# M623A.net
KiCad netlist of a schematic drawn in EAGLE
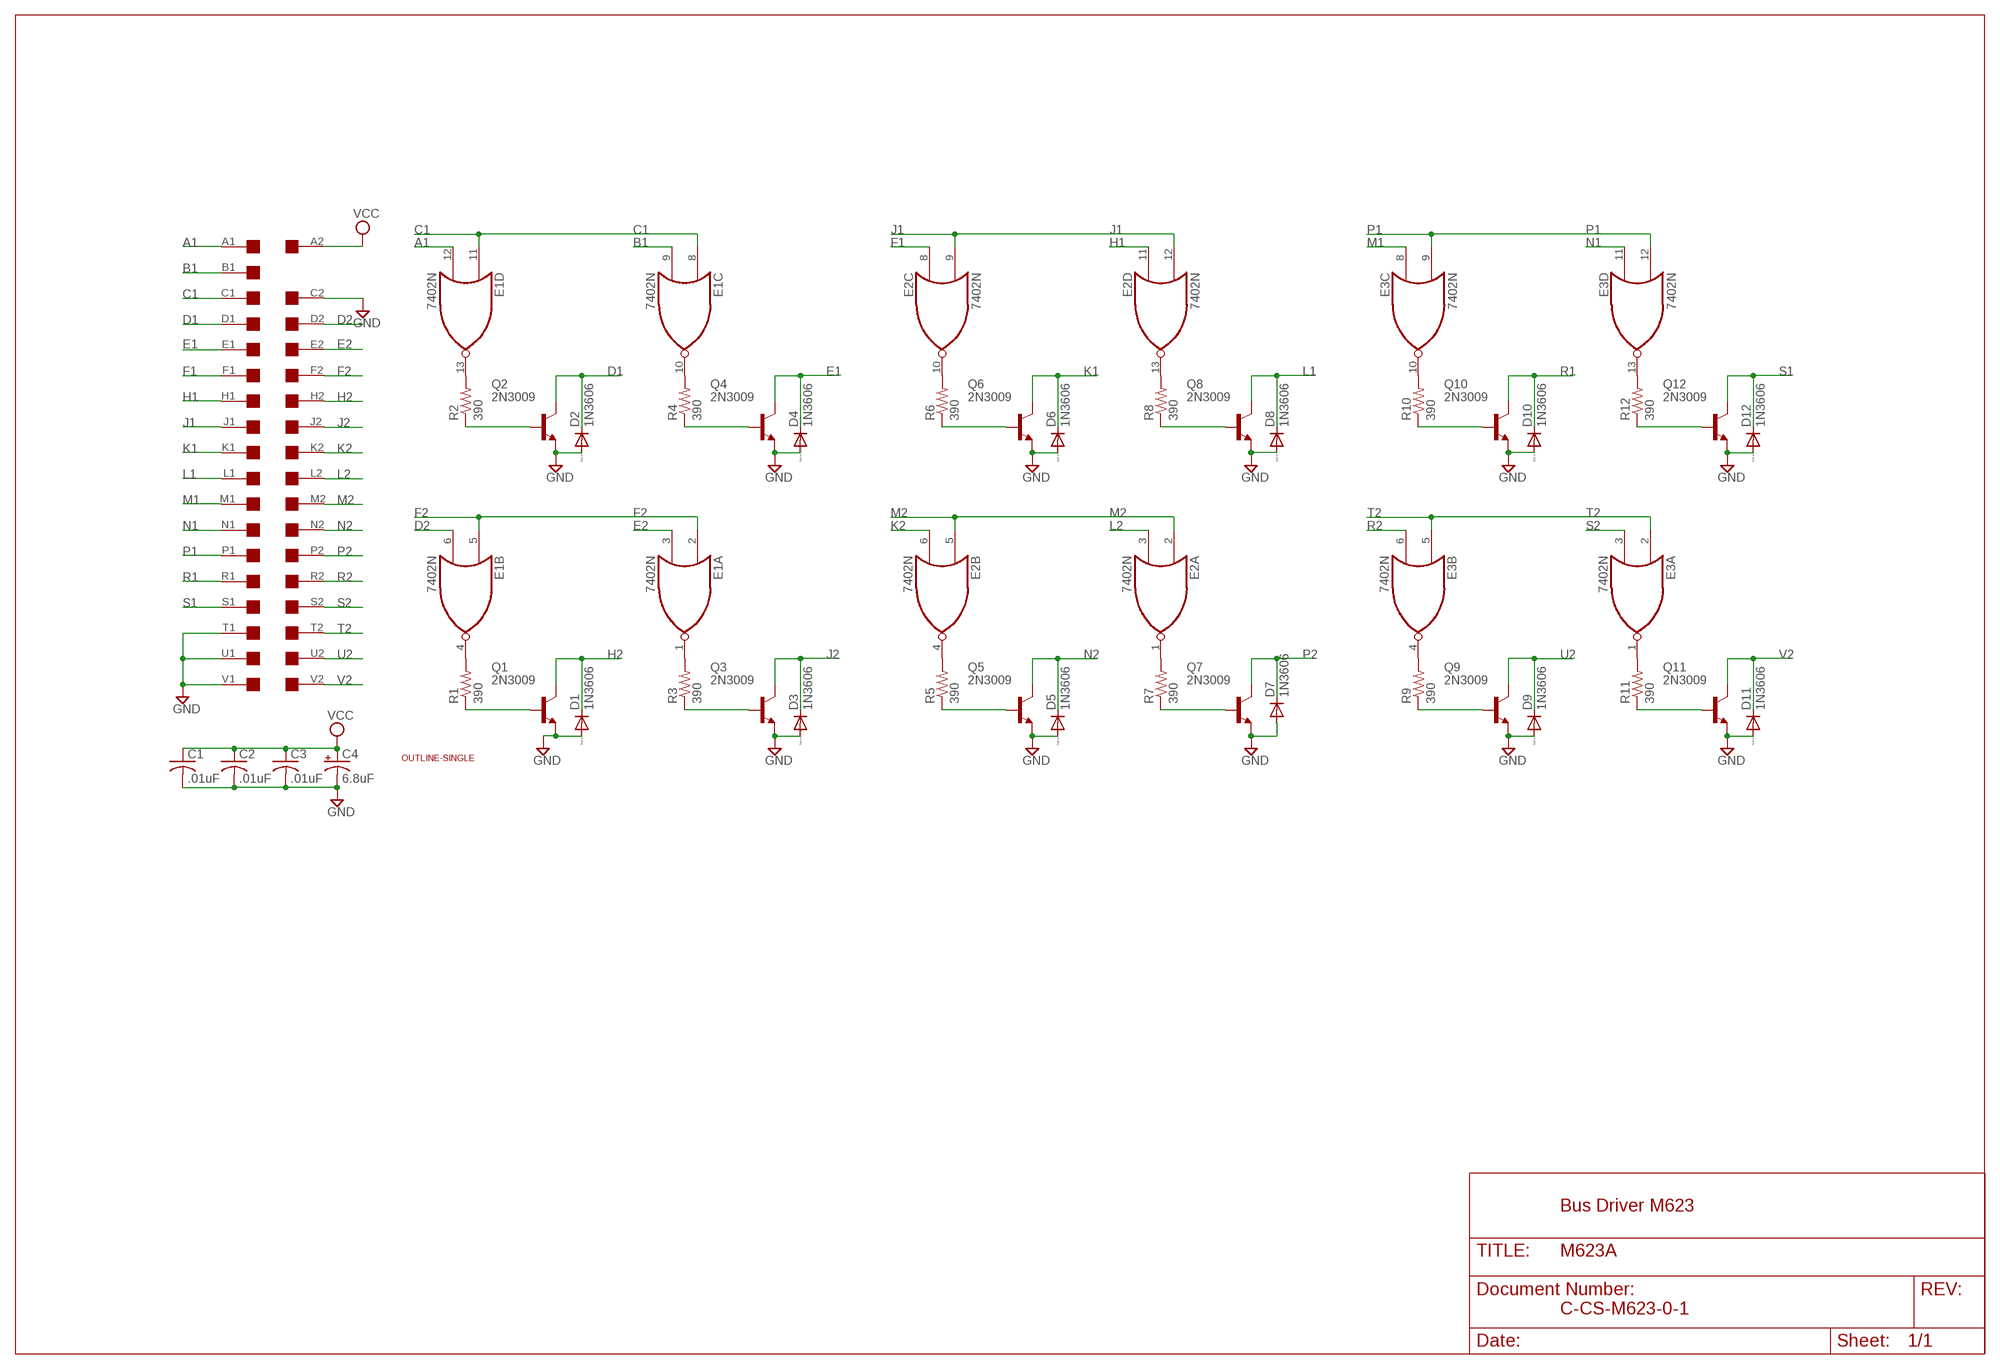
[diagram p0: schematic, sheet 1]

(export (version "E")
  (design (tool "Eeschema 10.0.6"))
  (components
    (comp (ref "C1")
      (value ".01uF")
      (footprint "eagle-import:C050-025X075")
      (libsource (lib "eagle-import") (part "C-US050-025X075"))
    )
    (comp (ref "C2")
      (value ".01uF")
      (footprint "eagle-import:C050-025X075")
      (libsource (lib "eagle-import") (part "C-US050-025X075"))
    )
    (comp (ref "C3")
      (value ".01uF")
      (footprint "eagle-import:C050-025X075")
      (libsource (lib "eagle-import") (part "C-US050-025X075"))
    )
    (comp (ref "C4")
      (value "6.8uF")
      (footprint "eagle-import:E15-5")
      (libsource (lib "eagle-import") (part "CPOL-USE15-5AXIAL"))
    )
    (comp (ref "D1")
      (value "1N3606")
      (footprint "eagle-import:DO35-10")
      (libsource (lib "eagle-import") (part "1N4148DO35-10"))
    )
    (comp (ref "D2")
      (value "1N3606")
      (footprint "eagle-import:DO35-10")
      (libsource (lib "eagle-import") (part "1N4148DO35-10"))
    )
    (comp (ref "D3")
      (value "1N3606")
      (footprint "eagle-import:DO35-10")
      (libsource (lib "eagle-import") (part "1N4148DO35-10"))
    )
    (comp (ref "D4")
      (value "1N3606")
      (footprint "eagle-import:DO35-10")
      (libsource (lib "eagle-import") (part "1N4148DO35-10"))
    )
    (comp (ref "D5")
      (value "1N3606")
      (footprint "eagle-import:DO35-10")
      (libsource (lib "eagle-import") (part "1N4148DO35-10"))
    )
    (comp (ref "D6")
      (value "1N3606")
      (footprint "eagle-import:DO35-10")
      (libsource (lib "eagle-import") (part "1N4148DO35-10"))
    )
    (comp (ref "D7")
      (value "1N3606")
      (footprint "eagle-import:DO35-10")
      (libsource (lib "eagle-import") (part "1N4148DO35-10"))
    )
    (comp (ref "D8")
      (value "1N3606")
      (footprint "eagle-import:DO35-10")
      (libsource (lib "eagle-import") (part "1N4148DO35-10"))
    )
    (comp (ref "D9")
      (value "1N3606")
      (footprint "eagle-import:DO35-10")
      (libsource (lib "eagle-import") (part "1N4148DO35-10"))
    )
    (comp (ref "D10")
      (value "1N3606")
      (footprint "eagle-import:DO35-10")
      (libsource (lib "eagle-import") (part "1N4148DO35-10"))
    )
    (comp (ref "D11")
      (value "1N3606")
      (footprint "eagle-import:DO35-10")
      (libsource (lib "eagle-import") (part "1N4148DO35-10"))
    )
    (comp (ref "D12")
      (value "1N3606")
      (footprint "eagle-import:DO35-10")
      (libsource (lib "eagle-import") (part "1N4148DO35-10"))
    )
    (comp (ref "E1")
      (value "7402N")
      (footprint "eagle-import:DIL14")
      (libsource (lib "eagle-import") (part "7402N"))
    )
    (comp (ref "E2")
      (value "7402N")
      (footprint "eagle-import:DIL14")
      (libsource (lib "eagle-import") (part "7402N"))
    )
    (comp (ref "E3")
      (value "7402N")
      (footprint "eagle-import:DIL14")
      (libsource (lib "eagle-import") (part "7402N"))
    )
    (comp (ref "Q1")
      (value "2N3009")
      (footprint "eagle-import:TO39")
      (libsource (lib "eagle-import") (part "-NPN-TO39-EBC2N1613"))
    )
    (comp (ref "Q2")
      (value "2N3009")
      (footprint "eagle-import:TO39")
      (libsource (lib "eagle-import") (part "-NPN-TO39-EBC2N1613"))
    )
    (comp (ref "Q3")
      (value "2N3009")
      (footprint "eagle-import:TO39")
      (libsource (lib "eagle-import") (part "-NPN-TO39-EBC2N1613"))
    )
    (comp (ref "Q4")
      (value "2N3009")
      (footprint "eagle-import:TO39")
      (libsource (lib "eagle-import") (part "-NPN-TO39-EBC2N1613"))
    )
    (comp (ref "Q5")
      (value "2N3009")
      (footprint "eagle-import:TO39")
      (libsource (lib "eagle-import") (part "-NPN-TO39-EBC2N1613"))
    )
    (comp (ref "Q6")
      (value "2N3009")
      (footprint "eagle-import:TO39")
      (libsource (lib "eagle-import") (part "-NPN-TO39-EBC2N1613"))
    )
    (comp (ref "Q7")
      (value "2N3009")
      (footprint "eagle-import:TO39")
      (libsource (lib "eagle-import") (part "-NPN-TO39-EBC2N1613"))
    )
    (comp (ref "Q8")
      (value "2N3009")
      (footprint "eagle-import:TO39")
      (libsource (lib "eagle-import") (part "-NPN-TO39-EBC2N1613"))
    )
    (comp (ref "Q9")
      (value "2N3009")
      (footprint "eagle-import:TO39")
      (libsource (lib "eagle-import") (part "-NPN-TO39-EBC2N1613"))
    )
    (comp (ref "Q10")
      (value "2N3009")
      (footprint "eagle-import:TO39")
      (libsource (lib "eagle-import") (part "-NPN-TO39-EBC2N1613"))
    )
    (comp (ref "Q11")
      (value "2N3009")
      (footprint "eagle-import:TO39")
      (libsource (lib "eagle-import") (part "-NPN-TO39-EBC2N1613"))
    )
    (comp (ref "Q12")
      (value "2N3009")
      (footprint "eagle-import:TO39")
      (libsource (lib "eagle-import") (part "-NPN-TO39-EBC2N1613"))
    )
    (comp (ref "R1")
      (value "390")
      (footprint "eagle-import:0207_10")
      (libsource (lib "eagle-import") (part "R-US_0207/10"))
    )
    (comp (ref "R2")
      (value "390")
      (footprint "eagle-import:0207_10")
      (libsource (lib "eagle-import") (part "R-US_0207/10"))
    )
    (comp (ref "R3")
      (value "390")
      (footprint "eagle-import:0207_10")
      (libsource (lib "eagle-import") (part "R-US_0207/10"))
    )
    (comp (ref "R4")
      (value "390")
      (footprint "eagle-import:0207_10")
      (libsource (lib "eagle-import") (part "R-US_0207/10"))
    )
    (comp (ref "R5")
      (value "390")
      (footprint "eagle-import:0207_10")
      (libsource (lib "eagle-import") (part "R-US_0207/10"))
    )
    (comp (ref "R6")
      (value "390")
      (footprint "eagle-import:0207_10")
      (libsource (lib "eagle-import") (part "R-US_0207/10"))
    )
    (comp (ref "R7")
      (value "390")
      (footprint "eagle-import:0207_10")
      (libsource (lib "eagle-import") (part "R-US_0207/10"))
    )
    (comp (ref "R8")
      (value "390")
      (footprint "eagle-import:0207_10")
      (libsource (lib "eagle-import") (part "R-US_0207/10"))
    )
    (comp (ref "R9")
      (value "390")
      (footprint "eagle-import:0207_10")
      (libsource (lib "eagle-import") (part "R-US_0207/10"))
    )
    (comp (ref "R10")
      (value "390")
      (footprint "eagle-import:0207_10")
      (libsource (lib "eagle-import") (part "R-US_0207/10"))
    )
    (comp (ref "R11")
      (value "390")
      (footprint "eagle-import:0207_10")
      (libsource (lib "eagle-import") (part "R-US_0207/10"))
    )
    (comp (ref "R12")
      (value "390")
      (footprint "eagle-import:0207_10")
      (libsource (lib "eagle-import") (part "R-US_0207/10"))
    )
    (comp (ref "U$1")
      (value "OUTLINE-SINGLE")
      (footprint "eagle-import:SINGLE")
      (libsource (lib "eagle-import") (part "OUTLINE-SINGLE"))
    )
    (comp (ref "U$4")
      (value "SINGLE")
      (footprint "eagle-import:EDGE-CON2")
      (libsource (lib "eagle-import") (part "SINGLE"))
    )
  )
  (nets
    (net (code "1") (name "/A1") (class "Default")
      (node (ref "E1") (pin "12") (pinfunction "I1_12") (pintype "input"))
      (node (ref "U$4") (pin "A1") (pinfunction "1_A1") (pintype "bidirectional"))
    )
    (net (code "2") (name "/B1") (class "Default")
      (node (ref "E1") (pin "9") (pinfunction "I1_9") (pintype "input"))
      (node (ref "U$4") (pin "B1") (pinfunction "1_B1") (pintype "bidirectional"))
    )
    (net (code "3") (name "/C1") (class "Default")
      (node (ref "E1") (pin "11") (pinfunction "I0_11") (pintype "input"))
      (node (ref "E1") (pin "8") (pinfunction "I0_8") (pintype "input"))
      (node (ref "U$4") (pin "C1") (pinfunction "1_C1") (pintype "bidirectional"))
    )
    (net (code "4") (name "/D1") (class "Default")
      (node (ref "D2") (pin "C") (pinfunction "C_C") (pintype "passive"))
      (node (ref "Q2") (pin "3") (pinfunction "C_3") (pintype "passive"))
      (node (ref "U$4") (pin "D1") (pinfunction "1_D1") (pintype "bidirectional"))
    )
    (net (code "5") (name "/D2") (class "Default")
      (node (ref "E1") (pin "6") (pinfunction "I1_6") (pintype "input"))
      (node (ref "U$4") (pin "D2") (pinfunction "1_D2") (pintype "bidirectional"))
    )
    (net (code "6") (name "/E1") (class "Default")
      (node (ref "D4") (pin "C") (pinfunction "C_C") (pintype "passive"))
      (node (ref "Q4") (pin "3") (pinfunction "C_3") (pintype "passive"))
      (node (ref "U$4") (pin "E1") (pinfunction "1_E1") (pintype "bidirectional"))
    )
    (net (code "7") (name "/E2") (class "Default")
      (node (ref "E1") (pin "3") (pinfunction "I1_3") (pintype "input"))
      (node (ref "U$4") (pin "E2") (pinfunction "1_E2") (pintype "bidirectional"))
    )
    (net (code "8") (name "/F1") (class "Default")
      (node (ref "E2") (pin "8") (pinfunction "I0_8") (pintype "input"))
      (node (ref "U$4") (pin "F1") (pinfunction "1_F1") (pintype "bidirectional"))
    )
    (net (code "9") (name "/F2") (class "Default")
      (node (ref "E1") (pin "2") (pinfunction "I0_2") (pintype "input"))
      (node (ref "E1") (pin "5") (pinfunction "I0_5") (pintype "input"))
      (node (ref "U$4") (pin "F2") (pinfunction "1_F2") (pintype "bidirectional"))
    )
    (net (code "10") (name "/H1") (class "Default")
      (node (ref "E2") (pin "11") (pinfunction "I0_11") (pintype "input"))
      (node (ref "U$4") (pin "H1") (pinfunction "1_H1") (pintype "bidirectional"))
    )
    (net (code "11") (name "/H2") (class "Default")
      (node (ref "D1") (pin "C") (pinfunction "C_C") (pintype "passive"))
      (node (ref "Q1") (pin "3") (pinfunction "C_3") (pintype "passive"))
      (node (ref "U$4") (pin "H2") (pinfunction "1_H2") (pintype "bidirectional"))
    )
    (net (code "12") (name "/J1") (class "Default")
      (node (ref "E2") (pin "12") (pinfunction "I1_12") (pintype "input"))
      (node (ref "E2") (pin "9") (pinfunction "I1_9") (pintype "input"))
      (node (ref "U$4") (pin "J1") (pinfunction "1_J1") (pintype "bidirectional"))
    )
    (net (code "13") (name "/J2") (class "Default")
      (node (ref "D3") (pin "C") (pinfunction "C_C") (pintype "passive"))
      (node (ref "Q3") (pin "3") (pinfunction "C_3") (pintype "passive"))
      (node (ref "U$4") (pin "J2") (pinfunction "1_J2") (pintype "bidirectional"))
    )
    (net (code "14") (name "/K1") (class "Default")
      (node (ref "D6") (pin "C") (pinfunction "C_C") (pintype "passive"))
      (node (ref "Q6") (pin "3") (pinfunction "C_3") (pintype "passive"))
      (node (ref "U$4") (pin "K1") (pinfunction "1_K1") (pintype "bidirectional"))
    )
    (net (code "15") (name "/K2") (class "Default")
      (node (ref "E2") (pin "6") (pinfunction "I1_6") (pintype "input"))
      (node (ref "U$4") (pin "K2") (pinfunction "1_K2") (pintype "bidirectional"))
    )
    (net (code "16") (name "/L1") (class "Default")
      (node (ref "D8") (pin "C") (pinfunction "C_C") (pintype "passive"))
      (node (ref "Q8") (pin "3") (pinfunction "C_3") (pintype "passive"))
      (node (ref "U$4") (pin "L1") (pinfunction "1_L1") (pintype "bidirectional"))
    )
    (net (code "17") (name "/L2") (class "Default")
      (node (ref "E2") (pin "3") (pinfunction "I1_3") (pintype "input"))
      (node (ref "U$4") (pin "L2") (pinfunction "1_L2") (pintype "bidirectional"))
    )
    (net (code "18") (name "/M1") (class "Default")
      (node (ref "E3") (pin "8") (pinfunction "I0_8") (pintype "input"))
      (node (ref "U$4") (pin "M1") (pinfunction "1_M1") (pintype "bidirectional"))
    )
    (net (code "19") (name "/M2") (class "Default")
      (node (ref "E2") (pin "2") (pinfunction "I0_2") (pintype "input"))
      (node (ref "E2") (pin "5") (pinfunction "I0_5") (pintype "input"))
      (node (ref "U$4") (pin "M2") (pinfunction "1_M2") (pintype "bidirectional"))
    )
    (net (code "20") (name "/N1") (class "Default")
      (node (ref "E3") (pin "11") (pinfunction "I0_11") (pintype "input"))
      (node (ref "U$4") (pin "N1") (pinfunction "1_N1") (pintype "bidirectional"))
    )
    (net (code "21") (name "/N2") (class "Default")
      (node (ref "D5") (pin "C") (pinfunction "C_C") (pintype "passive"))
      (node (ref "Q5") (pin "3") (pinfunction "C_3") (pintype "passive"))
      (node (ref "U$4") (pin "N2") (pinfunction "1_N2") (pintype "bidirectional"))
    )
    (net (code "22") (name "/P1") (class "Default")
      (node (ref "E3") (pin "12") (pinfunction "I1_12") (pintype "input"))
      (node (ref "E3") (pin "9") (pinfunction "I1_9") (pintype "input"))
      (node (ref "U$4") (pin "P1") (pinfunction "1_P1") (pintype "bidirectional"))
    )
    (net (code "23") (name "/P2") (class "Default")
      (node (ref "D7") (pin "C") (pinfunction "C_C") (pintype "passive"))
      (node (ref "Q7") (pin "3") (pinfunction "C_3") (pintype "passive"))
      (node (ref "U$4") (pin "P2") (pinfunction "1_P2") (pintype "bidirectional"))
    )
    (net (code "24") (name "/R1") (class "Default")
      (node (ref "D10") (pin "C") (pinfunction "C_C") (pintype "passive"))
      (node (ref "Q10") (pin "3") (pinfunction "C_3") (pintype "passive"))
      (node (ref "U$4") (pin "R1") (pinfunction "1_R1") (pintype "bidirectional"))
    )
    (net (code "25") (name "/R2") (class "Default")
      (node (ref "E3") (pin "6") (pinfunction "I1_6") (pintype "input"))
      (node (ref "U$4") (pin "R2") (pinfunction "1_R2") (pintype "bidirectional"))
    )
    (net (code "26") (name "/S1") (class "Default")
      (node (ref "D12") (pin "C") (pinfunction "C_C") (pintype "passive"))
      (node (ref "Q12") (pin "3") (pinfunction "C_3") (pintype "passive"))
      (node (ref "U$4") (pin "S1") (pinfunction "1_S1") (pintype "bidirectional"))
    )
    (net (code "27") (name "/S2") (class "Default")
      (node (ref "E3") (pin "3") (pinfunction "I1_3") (pintype "input"))
      (node (ref "U$4") (pin "S2") (pinfunction "1_S2") (pintype "bidirectional"))
    )
    (net (code "28") (name "/T2") (class "Default")
      (node (ref "E3") (pin "2") (pinfunction "I0_2") (pintype "input"))
      (node (ref "E3") (pin "5") (pinfunction "I0_5") (pintype "input"))
      (node (ref "U$4") (pin "T2") (pinfunction "1_T2") (pintype "bidirectional"))
    )
    (net (code "29") (name "/U2") (class "Default")
      (node (ref "D9") (pin "C") (pinfunction "C_C") (pintype "passive"))
      (node (ref "Q9") (pin "3") (pinfunction "C_3") (pintype "passive"))
      (node (ref "U$4") (pin "U2") (pinfunction "1_U2") (pintype "bidirectional"))
    )
    (net (code "30") (name "/V2") (class "Default")
      (node (ref "D11") (pin "C") (pinfunction "C_C") (pintype "passive"))
      (node (ref "Q11") (pin "3") (pinfunction "C_3") (pintype "passive"))
      (node (ref "U$4") (pin "V2") (pinfunction "1_V2") (pintype "bidirectional"))
    )
    (net (code "31") (name "GND") (class "Default")
      (node (ref "C1") (pin "2") (pinfunction "2_2") (pintype "passive"))
      (node (ref "C2") (pin "2") (pinfunction "2_2") (pintype "passive"))
      (node (ref "C3") (pin "2") (pinfunction "2_2") (pintype "passive"))
      (node (ref "C4") (pin "-") (pinfunction "-_-") (pintype "passive"))
      (node (ref "D1") (pin "A") (pinfunction "A_A") (pintype "passive"))
      (node (ref "D10") (pin "A") (pinfunction "A_A") (pintype "passive"))
      (node (ref "D11") (pin "A") (pinfunction "A_A") (pintype "passive"))
      (node (ref "D12") (pin "A") (pinfunction "A_A") (pintype "passive"))
      (node (ref "D2") (pin "A") (pinfunction "A_A") (pintype "passive"))
      (node (ref "D3") (pin "A") (pinfunction "A_A") (pintype "passive"))
      (node (ref "D4") (pin "A") (pinfunction "A_A") (pintype "passive"))
      (node (ref "D5") (pin "A") (pinfunction "A_A") (pintype "passive"))
      (node (ref "D6") (pin "A") (pinfunction "A_A") (pintype "passive"))
      (node (ref "D7") (pin "A") (pinfunction "A_A") (pintype "passive"))
      (node (ref "D8") (pin "A") (pinfunction "A_A") (pintype "passive"))
      (node (ref "D9") (pin "A") (pinfunction "A_A") (pintype "passive"))
      (node (ref "Q1") (pin "1") (pinfunction "E_1") (pintype "passive"))
      (node (ref "Q10") (pin "1") (pinfunction "E_1") (pintype "passive"))
      (node (ref "Q11") (pin "1") (pinfunction "E_1") (pintype "passive"))
      (node (ref "Q12") (pin "1") (pinfunction "E_1") (pintype "passive"))
      (node (ref "Q2") (pin "1") (pinfunction "E_1") (pintype "passive"))
      (node (ref "Q3") (pin "1") (pinfunction "E_1") (pintype "passive"))
      (node (ref "Q4") (pin "1") (pinfunction "E_1") (pintype "passive"))
      (node (ref "Q5") (pin "1") (pinfunction "E_1") (pintype "passive"))
      (node (ref "Q6") (pin "1") (pinfunction "E_1") (pintype "passive"))
      (node (ref "Q7") (pin "1") (pinfunction "E_1") (pintype "passive"))
      (node (ref "Q8") (pin "1") (pinfunction "E_1") (pintype "passive"))
      (node (ref "Q9") (pin "1") (pinfunction "E_1") (pintype "passive"))
      (node (ref "U$4") (pin "C2") (pinfunction "1_C2") (pintype "bidirectional"))
      (node (ref "U$4") (pin "T1") (pinfunction "1_T1") (pintype "bidirectional"))
      (node (ref "U$4") (pin "U1") (pinfunction "1_U1") (pintype "bidirectional"))
      (node (ref "U$4") (pin "V1") (pinfunction "1_V1") (pintype "bidirectional"))
    )
    (net (code "32") (name "Net-(E1A-O)") (class "Default")
      (node (ref "E1") (pin "1") (pinfunction "O_1") (pintype "output"))
      (node (ref "R3") (pin "2") (pinfunction "2_2") (pintype "passive"))
    )
    (net (code "33") (name "Net-(E1B-O)") (class "Default")
      (node (ref "E1") (pin "4") (pinfunction "O_4") (pintype "output"))
      (node (ref "R1") (pin "2") (pinfunction "2_2") (pintype "passive"))
    )
    (net (code "34") (name "Net-(E1C-O)") (class "Default")
      (node (ref "E1") (pin "10") (pinfunction "O_10") (pintype "output"))
      (node (ref "R4") (pin "2") (pinfunction "2_2") (pintype "passive"))
    )
    (net (code "35") (name "Net-(E1D-O)") (class "Default")
      (node (ref "E1") (pin "13") (pinfunction "O_13") (pintype "output"))
      (node (ref "R2") (pin "2") (pinfunction "2_2") (pintype "passive"))
    )
    (net (code "36") (name "Net-(E2A-O)") (class "Default")
      (node (ref "E2") (pin "1") (pinfunction "O_1") (pintype "output"))
      (node (ref "R7") (pin "2") (pinfunction "2_2") (pintype "passive"))
    )
    (net (code "37") (name "Net-(E2B-O)") (class "Default")
      (node (ref "E2") (pin "4") (pinfunction "O_4") (pintype "output"))
      (node (ref "R5") (pin "2") (pinfunction "2_2") (pintype "passive"))
    )
    (net (code "38") (name "Net-(E2C-O)") (class "Default")
      (node (ref "E2") (pin "10") (pinfunction "O_10") (pintype "output"))
      (node (ref "R6") (pin "2") (pinfunction "2_2") (pintype "passive"))
    )
    (net (code "39") (name "Net-(E2D-O)") (class "Default")
      (node (ref "E2") (pin "13") (pinfunction "O_13") (pintype "output"))
      (node (ref "R8") (pin "2") (pinfunction "2_2") (pintype "passive"))
    )
    (net (code "40") (name "Net-(E3A-O)") (class "Default")
      (node (ref "E3") (pin "1") (pinfunction "O_1") (pintype "output"))
      (node (ref "R11") (pin "2") (pinfunction "2_2") (pintype "passive"))
    )
    (net (code "41") (name "Net-(E3B-O)") (class "Default")
      (node (ref "E3") (pin "4") (pinfunction "O_4") (pintype "output"))
      (node (ref "R9") (pin "2") (pinfunction "2_2") (pintype "passive"))
    )
    (net (code "42") (name "Net-(E3C-O)") (class "Default")
      (node (ref "E3") (pin "10") (pinfunction "O_10") (pintype "output"))
      (node (ref "R10") (pin "2") (pinfunction "2_2") (pintype "passive"))
    )
    (net (code "43") (name "Net-(E3D-O)") (class "Default")
      (node (ref "E3") (pin "13") (pinfunction "O_13") (pintype "output"))
      (node (ref "R12") (pin "2") (pinfunction "2_2") (pintype "passive"))
    )
    (net (code "44") (name "Net-(Q1-B)") (class "Default")
      (node (ref "Q1") (pin "2") (pinfunction "B_2") (pintype "passive"))
      (node (ref "R1") (pin "1") (pinfunction "1_1") (pintype "passive"))
    )
    (net (code "45") (name "Net-(Q2-B)") (class "Default")
      (node (ref "Q2") (pin "2") (pinfunction "B_2") (pintype "passive"))
      (node (ref "R2") (pin "1") (pinfunction "1_1") (pintype "passive"))
    )
    (net (code "46") (name "Net-(Q3-B)") (class "Default")
      (node (ref "Q3") (pin "2") (pinfunction "B_2") (pintype "passive"))
      (node (ref "R3") (pin "1") (pinfunction "1_1") (pintype "passive"))
    )
    (net (code "47") (name "Net-(Q4-B)") (class "Default")
      (node (ref "Q4") (pin "2") (pinfunction "B_2") (pintype "passive"))
      (node (ref "R4") (pin "1") (pinfunction "1_1") (pintype "passive"))
    )
    (net (code "48") (name "Net-(Q5-B)") (class "Default")
      (node (ref "Q5") (pin "2") (pinfunction "B_2") (pintype "passive"))
      (node (ref "R5") (pin "1") (pinfunction "1_1") (pintype "passive"))
    )
    (net (code "49") (name "Net-(Q6-B)") (class "Default")
      (node (ref "Q6") (pin "2") (pinfunction "B_2") (pintype "passive"))
      (node (ref "R6") (pin "1") (pinfunction "1_1") (pintype "passive"))
    )
    (net (code "50") (name "Net-(Q7-B)") (class "Default")
      (node (ref "Q7") (pin "2") (pinfunction "B_2") (pintype "passive"))
      (node (ref "R7") (pin "1") (pinfunction "1_1") (pintype "passive"))
    )
    (net (code "51") (name "Net-(Q8-B)") (class "Default")
      (node (ref "Q8") (pin "2") (pinfunction "B_2") (pintype "passive"))
      (node (ref "R8") (pin "1") (pinfunction "1_1") (pintype "passive"))
    )
    (net (code "52") (name "Net-(Q9-B)") (class "Default")
      (node (ref "Q9") (pin "2") (pinfunction "B_2") (pintype "passive"))
      (node (ref "R9") (pin "1") (pinfunction "1_1") (pintype "passive"))
    )
    (net (code "53") (name "Net-(Q10-B)") (class "Default")
      (node (ref "Q10") (pin "2") (pinfunction "B_2") (pintype "passive"))
      (node (ref "R10") (pin "1") (pinfunction "1_1") (pintype "passive"))
    )
    (net (code "54") (name "Net-(Q11-B)") (class "Default")
      (node (ref "Q11") (pin "2") (pinfunction "B_2") (pintype "passive"))
      (node (ref "R11") (pin "1") (pinfunction "1_1") (pintype "passive"))
    )
    (net (code "55") (name "Net-(Q12-B)") (class "Default")
      (node (ref "Q12") (pin "2") (pinfunction "B_2") (pintype "passive"))
      (node (ref "R12") (pin "1") (pinfunction "1_1") (pintype "passive"))
    )
    (net (code "56") (name "VCC") (class "Default")
      (node (ref "C1") (pin "1") (pinfunction "1_1") (pintype "passive"))
      (node (ref "C2") (pin "1") (pinfunction "1_1") (pintype "passive"))
      (node (ref "C3") (pin "1") (pinfunction "1_1") (pintype "passive"))
      (node (ref "C4") (pin "+") (pinfunction "+_+") (pintype "passive"))
      (node (ref "U$4") (pin "A2") (pinfunction "1_A2") (pintype "bidirectional"))
    )
  )
)
